# FinalChannel.net
KiCad netlist of a schematic drawn in EAGLE
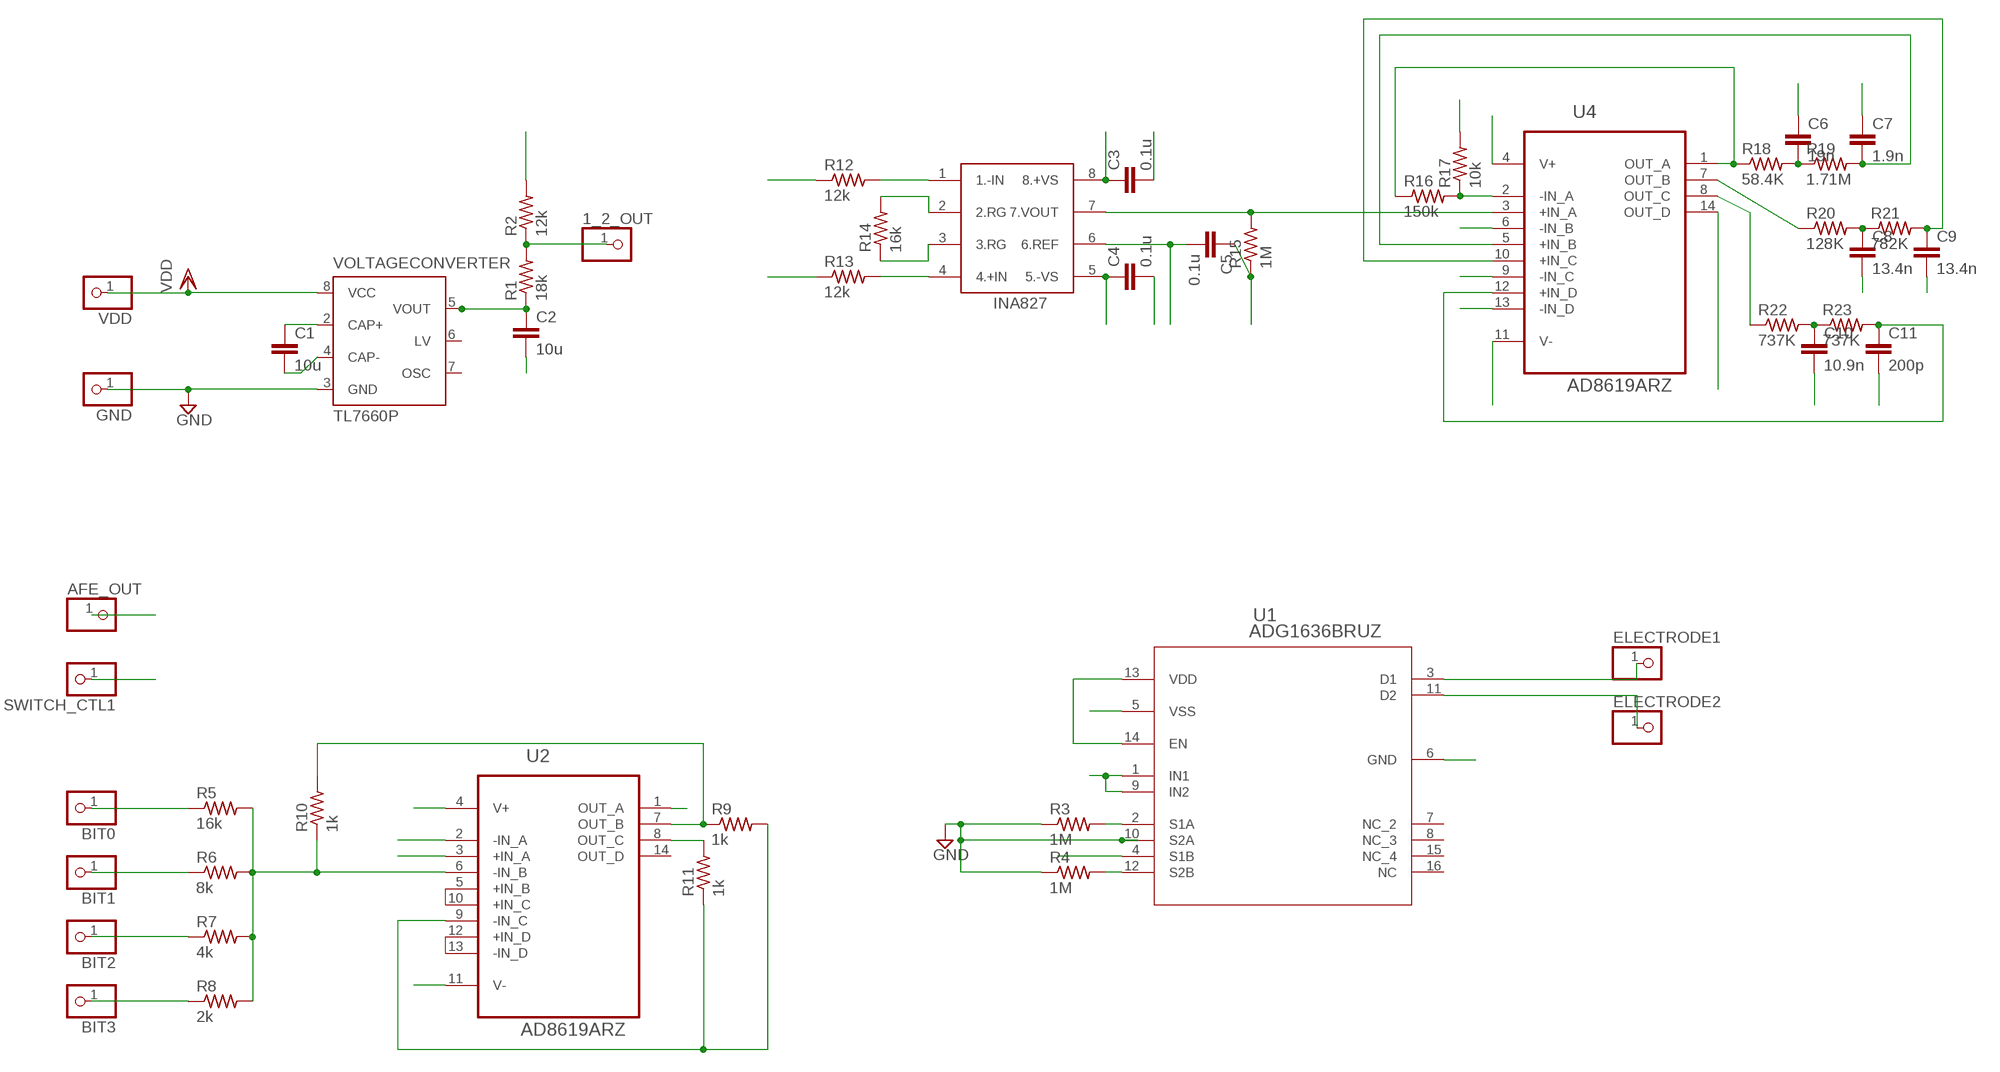
[diagram p0: schematic, sheet 1]

(export (version "E")
  (design (tool "Eeschema 10.0.6"))
  (components
    (comp (ref "1_2_OUT")
      (value "PINHD-1X1")
      (footprint "eagle-import:1X01")
      (libsource (lib "eagle-import") (part "PINHD-1X1"))
    )
    (comp (ref "AFE_OUT")
      (value "PINHD-1X1")
      (footprint "eagle-import:1X01")
      (libsource (lib "eagle-import") (part "PINHD-1X1"))
    )
    (comp (ref "BIT0")
      (value "PINHD-1X1")
      (footprint "eagle-import:1X01")
      (libsource (lib "eagle-import") (part "PINHD-1X1"))
    )
    (comp (ref "BIT1")
      (value "PINHD-1X1")
      (footprint "eagle-import:1X01")
      (libsource (lib "eagle-import") (part "PINHD-1X1"))
    )
    (comp (ref "BIT2")
      (value "PINHD-1X1")
      (footprint "eagle-import:1X01")
      (libsource (lib "eagle-import") (part "PINHD-1X1"))
    )
    (comp (ref "BIT3")
      (value "PINHD-1X1")
      (footprint "eagle-import:1X01")
      (libsource (lib "eagle-import") (part "PINHD-1X1"))
    )
    (comp (ref "C1")
      (value "10u")
      (footprint "eagle-import:C0805")
      (libsource (lib "eagle-import") (part "C-EUC0805"))
    )
    (comp (ref "C2")
      (value "10u")
      (footprint "eagle-import:C0805")
      (libsource (lib "eagle-import") (part "C-EUC0805"))
    )
    (comp (ref "C3")
      (value "0.1u")
      (footprint "eagle-import:C0805")
      (libsource (lib "eagle-import") (part "C-EUC0805"))
    )
    (comp (ref "C4")
      (value "0.1u")
      (footprint "eagle-import:C0805")
      (libsource (lib "eagle-import") (part "C-EUC0805"))
    )
    (comp (ref "C5")
      (value "0.1u")
      (footprint "eagle-import:C0805")
      (libsource (lib "eagle-import") (part "C-EUC0805"))
    )
    (comp (ref "C6")
      (value "19n")
      (footprint "eagle-import:C0805")
      (libsource (lib "eagle-import") (part "C-EUC0805"))
    )
    (comp (ref "C7")
      (value "1.9n")
      (footprint "eagle-import:C0805")
      (libsource (lib "eagle-import") (part "C-EUC0805"))
    )
    (comp (ref "C8")
      (value "13.4n")
      (footprint "eagle-import:C0805")
      (libsource (lib "eagle-import") (part "C-EUC0805"))
    )
    (comp (ref "C9")
      (value "13.4n")
      (footprint "eagle-import:C0805")
      (libsource (lib "eagle-import") (part "C-EUC0805"))
    )
    (comp (ref "C10")
      (value "10.9n")
      (footprint "eagle-import:C0805")
      (libsource (lib "eagle-import") (part "C-EUC0805"))
    )
    (comp (ref "C11")
      (value "200p")
      (footprint "eagle-import:C0805")
      (libsource (lib "eagle-import") (part "C-EUC0805"))
    )
    (comp (ref "ELECTRODE1")
      (value "PINHD-1X1")
      (footprint "eagle-import:1X01")
      (libsource (lib "eagle-import") (part "PINHD-1X1"))
    )
    (comp (ref "ELECTRODE2")
      (value "PINHD-1X1")
      (footprint "eagle-import:1X01")
      (libsource (lib "eagle-import") (part "PINHD-1X1"))
    )
    (comp (ref "GND")
      (value "PINHD-1X1")
      (footprint "eagle-import:1X01")
      (libsource (lib "eagle-import") (part "PINHD-1X1"))
    )
    (comp (ref "INA1")
      (value "INA827")
      (footprint "eagle-import:INA827")
      (libsource (lib "eagle-import") (part "INA827"))
    )
    (comp (ref "R1")
      (value "18k")
      (footprint "eagle-import:R0805")
      (libsource (lib "eagle-import") (part "R-US_R0805"))
    )
    (comp (ref "R2")
      (value "12k")
      (footprint "eagle-import:R0805")
      (libsource (lib "eagle-import") (part "R-US_R0805"))
    )
    (comp (ref "R3")
      (value "1M")
      (footprint "eagle-import:M0805")
      (libsource (lib "eagle-import") (part "R-US_M0805"))
    )
    (comp (ref "R4")
      (value "1M")
      (footprint "eagle-import:M0805")
      (libsource (lib "eagle-import") (part "R-US_M0805"))
    )
    (comp (ref "R5")
      (value "16k")
      (footprint "eagle-import:M0805")
      (libsource (lib "eagle-import") (part "R-US_M0805"))
    )
    (comp (ref "R6")
      (value "8k")
      (footprint "eagle-import:M0805")
      (libsource (lib "eagle-import") (part "R-US_M0805"))
    )
    (comp (ref "R7")
      (value "4k")
      (footprint "eagle-import:M0805")
      (libsource (lib "eagle-import") (part "R-US_M0805"))
    )
    (comp (ref "R8")
      (value "2k")
      (footprint "eagle-import:M0805")
      (libsource (lib "eagle-import") (part "R-US_M0805"))
    )
    (comp (ref "R9")
      (value "1k")
      (footprint "eagle-import:M0805")
      (libsource (lib "eagle-import") (part "R-US_M0805"))
    )
    (comp (ref "R10")
      (value "1k")
      (footprint "eagle-import:M0805")
      (libsource (lib "eagle-import") (part "R-US_M0805"))
    )
    (comp (ref "R11")
      (value "1k")
      (footprint "eagle-import:M0805")
      (libsource (lib "eagle-import") (part "R-US_M0805"))
    )
    (comp (ref "R12")
      (value "12k")
      (footprint "eagle-import:M0805")
      (libsource (lib "eagle-import") (part "R-US_M0805"))
    )
    (comp (ref "R13")
      (value "12k")
      (footprint "eagle-import:M0805")
      (libsource (lib "eagle-import") (part "R-US_M0805"))
    )
    (comp (ref "R14")
      (value "16k")
      (footprint "eagle-import:M0805")
      (libsource (lib "eagle-import") (part "R-US_M0805"))
    )
    (comp (ref "R15")
      (value "1M")
      (footprint "eagle-import:M0805")
      (libsource (lib "eagle-import") (part "R-US_M0805"))
    )
    (comp (ref "R16")
      (value "150k")
      (footprint "eagle-import:M0805")
      (libsource (lib "eagle-import") (part "R-US_M0805"))
    )
    (comp (ref "R17")
      (value "10k")
      (footprint "eagle-import:M0805")
      (libsource (lib "eagle-import") (part "R-US_M0805"))
    )
    (comp (ref "R18")
      (value "58.4K")
      (footprint "eagle-import:M0805")
      (libsource (lib "eagle-import") (part "R-US_M0805"))
    )
    (comp (ref "R19")
      (value "1.71M")
      (footprint "eagle-import:M0805")
      (libsource (lib "eagle-import") (part "R-US_M0805"))
    )
    (comp (ref "R20")
      (value "128K")
      (footprint "eagle-import:M0805")
      (libsource (lib "eagle-import") (part "R-US_M0805"))
    )
    (comp (ref "R21")
      (value "782K")
      (footprint "eagle-import:M0805")
      (libsource (lib "eagle-import") (part "R-US_M0805"))
    )
    (comp (ref "R22")
      (value "737K")
      (footprint "eagle-import:M0805")
      (libsource (lib "eagle-import") (part "R-US_M0805"))
    )
    (comp (ref "R23")
      (value "737K")
      (footprint "eagle-import:M0805")
      (libsource (lib "eagle-import") (part "R-US_M0805"))
    )
    (comp (ref "SWITCH_CTL1")
      (value "PINHD-1X1")
      (footprint "eagle-import:1X01")
      (libsource (lib "eagle-import") (part "PINHD-1X1"))
    )
    (comp (ref "U1")
      (value "ADG1636BRUZ")
      (footprint "eagle-import:RU_16")
      (libsource (lib "eagle-import") (part "ADG1636BRUZ"))
    )
    (comp (ref "U2")
      (value "AD8619ARZ")
      (footprint "eagle-import:SOIC127P600X175-14N")
      (fields (field (name "MF") "Analog Devices"))
      (libsource (lib "eagle-import") (part "AD8619ARZ"))
    )
    (comp (ref "U4")
      (value "AD8619ARZ")
      (footprint "eagle-import:SOIC127P600X175-14N")
      (fields (field (name "MF") "Analog Devices"))
      (libsource (lib "eagle-import") (part "AD8619ARZ"))
    )
    (comp (ref "VDD")
      (value "PINHD-1X1")
      (footprint "eagle-import:1X01")
      (libsource (lib "eagle-import") (part "PINHD-1X1"))
    )
    (comp (ref "VOLTAGECONVERTER")
      (value "TL7660P")
      (footprint "eagle-import:DIL08")
      (fields (field (name "MPN") "TL7660CP"))
      (libsource (lib "eagle-import") (part "TL7660P"))
    )
  )
  (nets
    (net (code "1") (name "/AFE_OUT") (class "Default")
      (node (ref "AFE_OUT") (pin "1") (pinfunction "1_1") (pintype "passive"))
      (node (ref "C10") (pin "2") (pinfunction "2_2") (pintype "passive"))
      (node (ref "U4") (pin "13") (pinfunction "-IN_D_13") (pintype "input"))
      (node (ref "U4") (pin "14") (pinfunction "OUT_D_14") (pintype "output"))
    )
    (net (code "2") (name "/CTL1") (class "Default")
      (node (ref "SWITCH_CTL1") (pin "1") (pinfunction "1_1") (pintype "passive"))
      (node (ref "U1") (pin "1") (pinfunction "IN1_1") (pintype "passive"))
      (node (ref "U1") (pin "9") (pinfunction "IN2_9") (pintype "passive"))
    )
    (net (code "3") (name "/IN_N") (class "Default")
      (node (ref "R12") (pin "1") (pinfunction "1_1") (pintype "passive"))
      (node (ref "R4") (pin "2") (pinfunction "2_2") (pintype "passive"))
      (node (ref "U1") (pin "12") (pinfunction "S2B_12") (pintype "passive"))
    )
    (net (code "4") (name "/IN_P") (class "Default")
      (node (ref "R13") (pin "1") (pinfunction "1_1") (pintype "passive"))
      (node (ref "R3") (pin "2") (pinfunction "2_2") (pintype "passive"))
      (node (ref "U1") (pin "2") (pinfunction "S1A_2") (pintype "passive"))
    )
    (net (code "5") (name "/OUT_B") (class "Default")
      (node (ref "C6") (pin "1") (pinfunction "1_1") (pintype "passive"))
      (node (ref "R20") (pin "1") (pinfunction "1_1") (pintype "passive"))
      (node (ref "U4") (pin "6") (pinfunction "-IN_B_6") (pintype "input"))
      (node (ref "U4") (pin "7") (pinfunction "OUT_B_7") (pintype "output"))
    )
    (net (code "6") (name "/OUT_C") (class "Default")
      (node (ref "C8") (pin "2") (pinfunction "2_2") (pintype "passive"))
      (node (ref "R22") (pin "1") (pinfunction "1_1") (pintype "passive"))
      (node (ref "U4") (pin "8") (pinfunction "OUT_C_8") (pintype "output"))
      (node (ref "U4") (pin "9") (pinfunction "-IN_C_9") (pintype "input"))
    )
    (net (code "7") (name "/P_GEN_OUT") (class "Default")
      (node (ref "R11") (pin "2") (pinfunction "2_2") (pintype "passive"))
      (node (ref "U1") (pin "4") (pinfunction "S1B_4") (pintype "passive"))
      (node (ref "U2") (pin "8") (pinfunction "OUT_C_8") (pintype "output"))
    )
    (net (code "8") (name "/SINGLE-") (class "Default")
      (node (ref "C5") (pin "1") (pinfunction "1_1") (pintype "passive"))
      (node (ref "R15") (pin "1") (pinfunction "1_1") (pintype "passive"))
      (node (ref "U2") (pin "2") (pinfunction "-IN_A_2") (pintype "input"))
    )
    (net (code "9") (name "/SINGLE_OUT") (class "Default")
      (node (ref "C5") (pin "2") (pinfunction "2_2") (pintype "passive"))
      (node (ref "INA1") (pin "6") (pinfunction "6.REF_6") (pintype "bidirectional"))
      (node (ref "U2") (pin "1") (pinfunction "OUT_A_1") (pintype "output"))
    )
    (net (code "10") (name "/VDD-") (class "Default")
      (node (ref "C2") (pin "1") (pinfunction "1_1") (pintype "passive"))
      (node (ref "C4") (pin "1") (pinfunction "1_1") (pintype "passive"))
      (node (ref "INA1") (pin "5") (pinfunction "5.-VS_5") (pintype "bidirectional"))
      (node (ref "R1") (pin "1") (pinfunction "1_1") (pintype "passive"))
      (node (ref "U1") (pin "5") (pinfunction "VSS_5") (pintype "passive"))
      (node (ref "U2") (pin "11") (pinfunction "V-_11") (pintype "power_in"))
      (node (ref "U4") (pin "11") (pinfunction "V-_11") (pintype "power_in"))
      (node (ref "VOLTAGECONVERTER") (pin "5") (pinfunction "VOUT_5") (pintype "passive"))
    )
    (net (code "11") (name "GND") (class "Default")
      (node (ref "C11") (pin "2") (pinfunction "2_2") (pintype "passive"))
      (node (ref "C2") (pin "2") (pinfunction "2_2") (pintype "passive"))
      (node (ref "C3") (pin "2") (pinfunction "2_2") (pintype "passive"))
      (node (ref "C4") (pin "2") (pinfunction "2_2") (pintype "passive"))
      (node (ref "C7") (pin "1") (pinfunction "1_1") (pintype "passive"))
      (node (ref "C9") (pin "2") (pinfunction "2_2") (pintype "passive"))
      (node (ref "GND") (pin "1") (pinfunction "1_1") (pintype "passive"))
      (node (ref "R17") (pin "2") (pinfunction "2_2") (pintype "passive"))
      (node (ref "R2") (pin "2") (pinfunction "2_2") (pintype "passive"))
      (node (ref "R3") (pin "1") (pinfunction "1_1") (pintype "passive"))
      (node (ref "R4") (pin "1") (pinfunction "1_1") (pintype "passive"))
      (node (ref "U1") (pin "10") (pinfunction "S2A_10") (pintype "passive"))
      (node (ref "U1") (pin "6") (pinfunction "GND_6") (pintype "passive"))
      (node (ref "U2") (pin "10") (pinfunction "+IN_C_10") (pintype "input"))
      (node (ref "U2") (pin "12") (pinfunction "+IN_D_12") (pintype "input"))
      (node (ref "U2") (pin "13") (pinfunction "-IN_D_13") (pintype "input"))
      (node (ref "U2") (pin "3") (pinfunction "+IN_A_3") (pintype "input"))
      (node (ref "U2") (pin "5") (pinfunction "+IN_B_5") (pintype "input"))
      (node (ref "VOLTAGECONVERTER") (pin "3") (pinfunction "GND_3") (pintype "power_in"))
    )
    (net (code "12") (name "Net-(1_2_OUT-Pad1)") (class "Default")
      (node (ref "1_2_OUT") (pin "1") (pinfunction "1_1") (pintype "passive"))
      (node (ref "R1") (pin "2") (pinfunction "2_2") (pintype "passive"))
      (node (ref "R2") (pin "1") (pinfunction "1_1") (pintype "passive"))
    )
    (net (code "13") (name "Net-(BIT0-Pad1)") (class "Default")
      (node (ref "BIT0") (pin "1") (pinfunction "1_1") (pintype "passive"))
      (node (ref "R5") (pin "1") (pinfunction "1_1") (pintype "passive"))
    )
    (net (code "14") (name "Net-(BIT1-Pad1)") (class "Default")
      (node (ref "BIT1") (pin "1") (pinfunction "1_1") (pintype "passive"))
      (node (ref "R6") (pin "1") (pinfunction "1_1") (pintype "passive"))
    )
    (net (code "15") (name "Net-(BIT2-Pad1)") (class "Default")
      (node (ref "BIT2") (pin "1") (pinfunction "1_1") (pintype "passive"))
      (node (ref "R7") (pin "1") (pinfunction "1_1") (pintype "passive"))
    )
    (net (code "16") (name "Net-(BIT3-Pad1)") (class "Default")
      (node (ref "BIT3") (pin "1") (pinfunction "1_1") (pintype "passive"))
      (node (ref "R8") (pin "1") (pinfunction "1_1") (pintype "passive"))
    )
    (net (code "17") (name "Net-(C6-Pad2)") (class "Default")
      (node (ref "C6") (pin "2") (pinfunction "2_2") (pintype "passive"))
      (node (ref "R18") (pin "2") (pinfunction "2_2") (pintype "passive"))
      (node (ref "R19") (pin "1") (pinfunction "1_1") (pintype "passive"))
    )
    (net (code "18") (name "Net-(C8-Pad1)") (class "Default")
      (node (ref "C8") (pin "1") (pinfunction "1_1") (pintype "passive"))
      (node (ref "R20") (pin "2") (pinfunction "2_2") (pintype "passive"))
      (node (ref "R21") (pin "1") (pinfunction "1_1") (pintype "passive"))
    )
    (net (code "19") (name "Net-(C10-Pad1)") (class "Default")
      (node (ref "C10") (pin "1") (pinfunction "1_1") (pintype "passive"))
      (node (ref "R22") (pin "2") (pinfunction "2_2") (pintype "passive"))
      (node (ref "R23") (pin "1") (pinfunction "1_1") (pintype "passive"))
    )
    (net (code "20") (name "Net-(INA1-1.-IN)") (class "Default")
      (node (ref "INA1") (pin "1") (pinfunction "1.-IN_1") (pintype "bidirectional"))
      (node (ref "R12") (pin "2") (pinfunction "2_2") (pintype "passive"))
    )
    (net (code "21") (name "Net-(INA1-2.RG)") (class "Default")
      (node (ref "INA1") (pin "2") (pinfunction "2.RG_2") (pintype "bidirectional"))
      (node (ref "R14") (pin "2") (pinfunction "2_2") (pintype "passive"))
    )
    (net (code "22") (name "Net-(INA1-3.RG)") (class "Default")
      (node (ref "INA1") (pin "3") (pinfunction "3.RG_3") (pintype "bidirectional"))
      (node (ref "R14") (pin "1") (pinfunction "1_1") (pintype "passive"))
    )
    (net (code "23") (name "Net-(INA1-4.+IN)") (class "Default")
      (node (ref "INA1") (pin "4") (pinfunction "4.+IN_4") (pintype "bidirectional"))
      (node (ref "R13") (pin "2") (pinfunction "2_2") (pintype "passive"))
    )
    (net (code "24") (name "Net-(INA1-7.VOUT)") (class "Default")
      (node (ref "INA1") (pin "7") (pinfunction "7.VOUT_7") (pintype "bidirectional"))
      (node (ref "R15") (pin "2") (pinfunction "2_2") (pintype "passive"))
      (node (ref "U4") (pin "3") (pinfunction "+IN_A_3") (pintype "input"))
    )
    (net (code "25") (name "Net-(U1-D1)") (class "Default")
      (node (ref "ELECTRODE1") (pin "1") (pinfunction "1_1") (pintype "passive"))
      (node (ref "U1") (pin "3") (pinfunction "D1_3") (pintype "passive"))
    )
    (net (code "26") (name "Net-(U1-D2)") (class "Default")
      (node (ref "ELECTRODE2") (pin "1") (pinfunction "1_1") (pintype "passive"))
      (node (ref "U1") (pin "11") (pinfunction "D2_11") (pintype "passive"))
    )
    (net (code "27") (name "Net-(U2--IN_B)") (class "Default")
      (node (ref "R10") (pin "1") (pinfunction "1_1") (pintype "passive"))
      (node (ref "R5") (pin "2") (pinfunction "2_2") (pintype "passive"))
      (node (ref "R6") (pin "2") (pinfunction "2_2") (pintype "passive"))
      (node (ref "R7") (pin "2") (pinfunction "2_2") (pintype "passive"))
      (node (ref "R8") (pin "2") (pinfunction "2_2") (pintype "passive"))
      (node (ref "U2") (pin "6") (pinfunction "-IN_B_6") (pintype "input"))
    )
    (net (code "28") (name "Net-(U2--IN_C)") (class "Default")
      (node (ref "R11") (pin "1") (pinfunction "1_1") (pintype "passive"))
      (node (ref "R9") (pin "2") (pinfunction "2_2") (pintype "passive"))
      (node (ref "U2") (pin "9") (pinfunction "-IN_C_9") (pintype "input"))
    )
    (net (code "29") (name "Net-(U2-OUT_B)") (class "Default")
      (node (ref "R10") (pin "2") (pinfunction "2_2") (pintype "passive"))
      (node (ref "R9") (pin "1") (pinfunction "1_1") (pintype "passive"))
      (node (ref "U2") (pin "7") (pinfunction "OUT_B_7") (pintype "output"))
    )
    (net (code "30") (name "Net-(U4-+IN_B)") (class "Default")
      (node (ref "C7") (pin "2") (pinfunction "2_2") (pintype "passive"))
      (node (ref "R19") (pin "2") (pinfunction "2_2") (pintype "passive"))
      (node (ref "U4") (pin "5") (pinfunction "+IN_B_5") (pintype "input"))
    )
    (net (code "31") (name "Net-(U4-+IN_C)") (class "Default")
      (node (ref "C9") (pin "1") (pinfunction "1_1") (pintype "passive"))
      (node (ref "R21") (pin "2") (pinfunction "2_2") (pintype "passive"))
      (node (ref "U4") (pin "10") (pinfunction "+IN_C_10") (pintype "input"))
    )
    (net (code "32") (name "Net-(U4-+IN_D)") (class "Default")
      (node (ref "C11") (pin "1") (pinfunction "1_1") (pintype "passive"))
      (node (ref "R23") (pin "2") (pinfunction "2_2") (pintype "passive"))
      (node (ref "U4") (pin "12") (pinfunction "+IN_D_12") (pintype "input"))
    )
    (net (code "33") (name "Net-(U4--IN_A)") (class "Default")
      (node (ref "R16") (pin "2") (pinfunction "2_2") (pintype "passive"))
      (node (ref "R17") (pin "1") (pinfunction "1_1") (pintype "passive"))
      (node (ref "U4") (pin "2") (pinfunction "-IN_A_2") (pintype "input"))
    )
    (net (code "34") (name "Net-(U4-OUT_A)") (class "Default")
      (node (ref "R16") (pin "1") (pinfunction "1_1") (pintype "passive"))
      (node (ref "R18") (pin "1") (pinfunction "1_1") (pintype "passive"))
      (node (ref "U4") (pin "1") (pinfunction "OUT_A_1") (pintype "output"))
    )
    (net (code "35") (name "Net-(VOLTAGECONVERTER-CAP+)") (class "Default")
      (node (ref "C1") (pin "1") (pinfunction "1_1") (pintype "passive"))
      (node (ref "VOLTAGECONVERTER") (pin "2") (pinfunction "CAP+_2") (pintype "passive"))
    )
    (net (code "36") (name "Net-(VOLTAGECONVERTER-CAP-)") (class "Default")
      (node (ref "C1") (pin "2") (pinfunction "2_2") (pintype "passive"))
      (node (ref "VOLTAGECONVERTER") (pin "4") (pinfunction "CAP-_4") (pintype "passive"))
    )
    (net (code "37") (name "VDD") (class "Default")
      (node (ref "C3") (pin "1") (pinfunction "1_1") (pintype "passive"))
      (node (ref "INA1") (pin "8") (pinfunction "8.+VS_8") (pintype "bidirectional"))
      (node (ref "U1") (pin "13") (pinfunction "VDD_13") (pintype "passive"))
      (node (ref "U1") (pin "14") (pinfunction "EN_14") (pintype "passive"))
      (node (ref "U2") (pin "4") (pinfunction "V+_4") (pintype "power_in"))
      (node (ref "U4") (pin "4") (pinfunction "V+_4") (pintype "power_in"))
      (node (ref "VDD") (pin "1") (pinfunction "1_1") (pintype "passive"))
      (node (ref "VOLTAGECONVERTER") (pin "8") (pinfunction "VCC_8") (pintype "power_in"))
    )
    (net (code "38") (name "unconnected-(U1-NC-Pad16)") (class "Default")
      (node (ref "U1") (pin "16") (pinfunction "NC_16") (pintype "passive"))
    )
    (net (code "39") (name "unconnected-(U1-NC_2-Pad7)") (class "Default")
      (node (ref "U1") (pin "7") (pinfunction "NC_2_7") (pintype "passive"))
    )
    (net (code "40") (name "unconnected-(U1-NC_3-Pad8)") (class "Default")
      (node (ref "U1") (pin "8") (pinfunction "NC_3_8") (pintype "passive"))
    )
    (net (code "41") (name "unconnected-(U1-NC_4-Pad15)") (class "Default")
      (node (ref "U1") (pin "15") (pinfunction "NC_4_15") (pintype "passive"))
    )
    (net (code "42") (name "unconnected-(U2-OUT_D-Pad14)") (class "Default")
      (node (ref "U2") (pin "14") (pinfunction "OUT_D_14") (pintype "output"))
    )
    (net (code "43") (name "unconnected-(VOLTAGECONVERTER-LV-Pad6)") (class "Default")
      (node (ref "VOLTAGECONVERTER") (pin "6") (pinfunction "LV_6") (pintype "passive"))
    )
    (net (code "44") (name "unconnected-(VOLTAGECONVERTER-OSC-Pad7)") (class "Default")
      (node (ref "VOLTAGECONVERTER") (pin "7") (pinfunction "OSC_7") (pintype "input"))
    )
  )
)
